# Power_Generation.net
KiCad netlist of a schematic drawn in Altium Designer
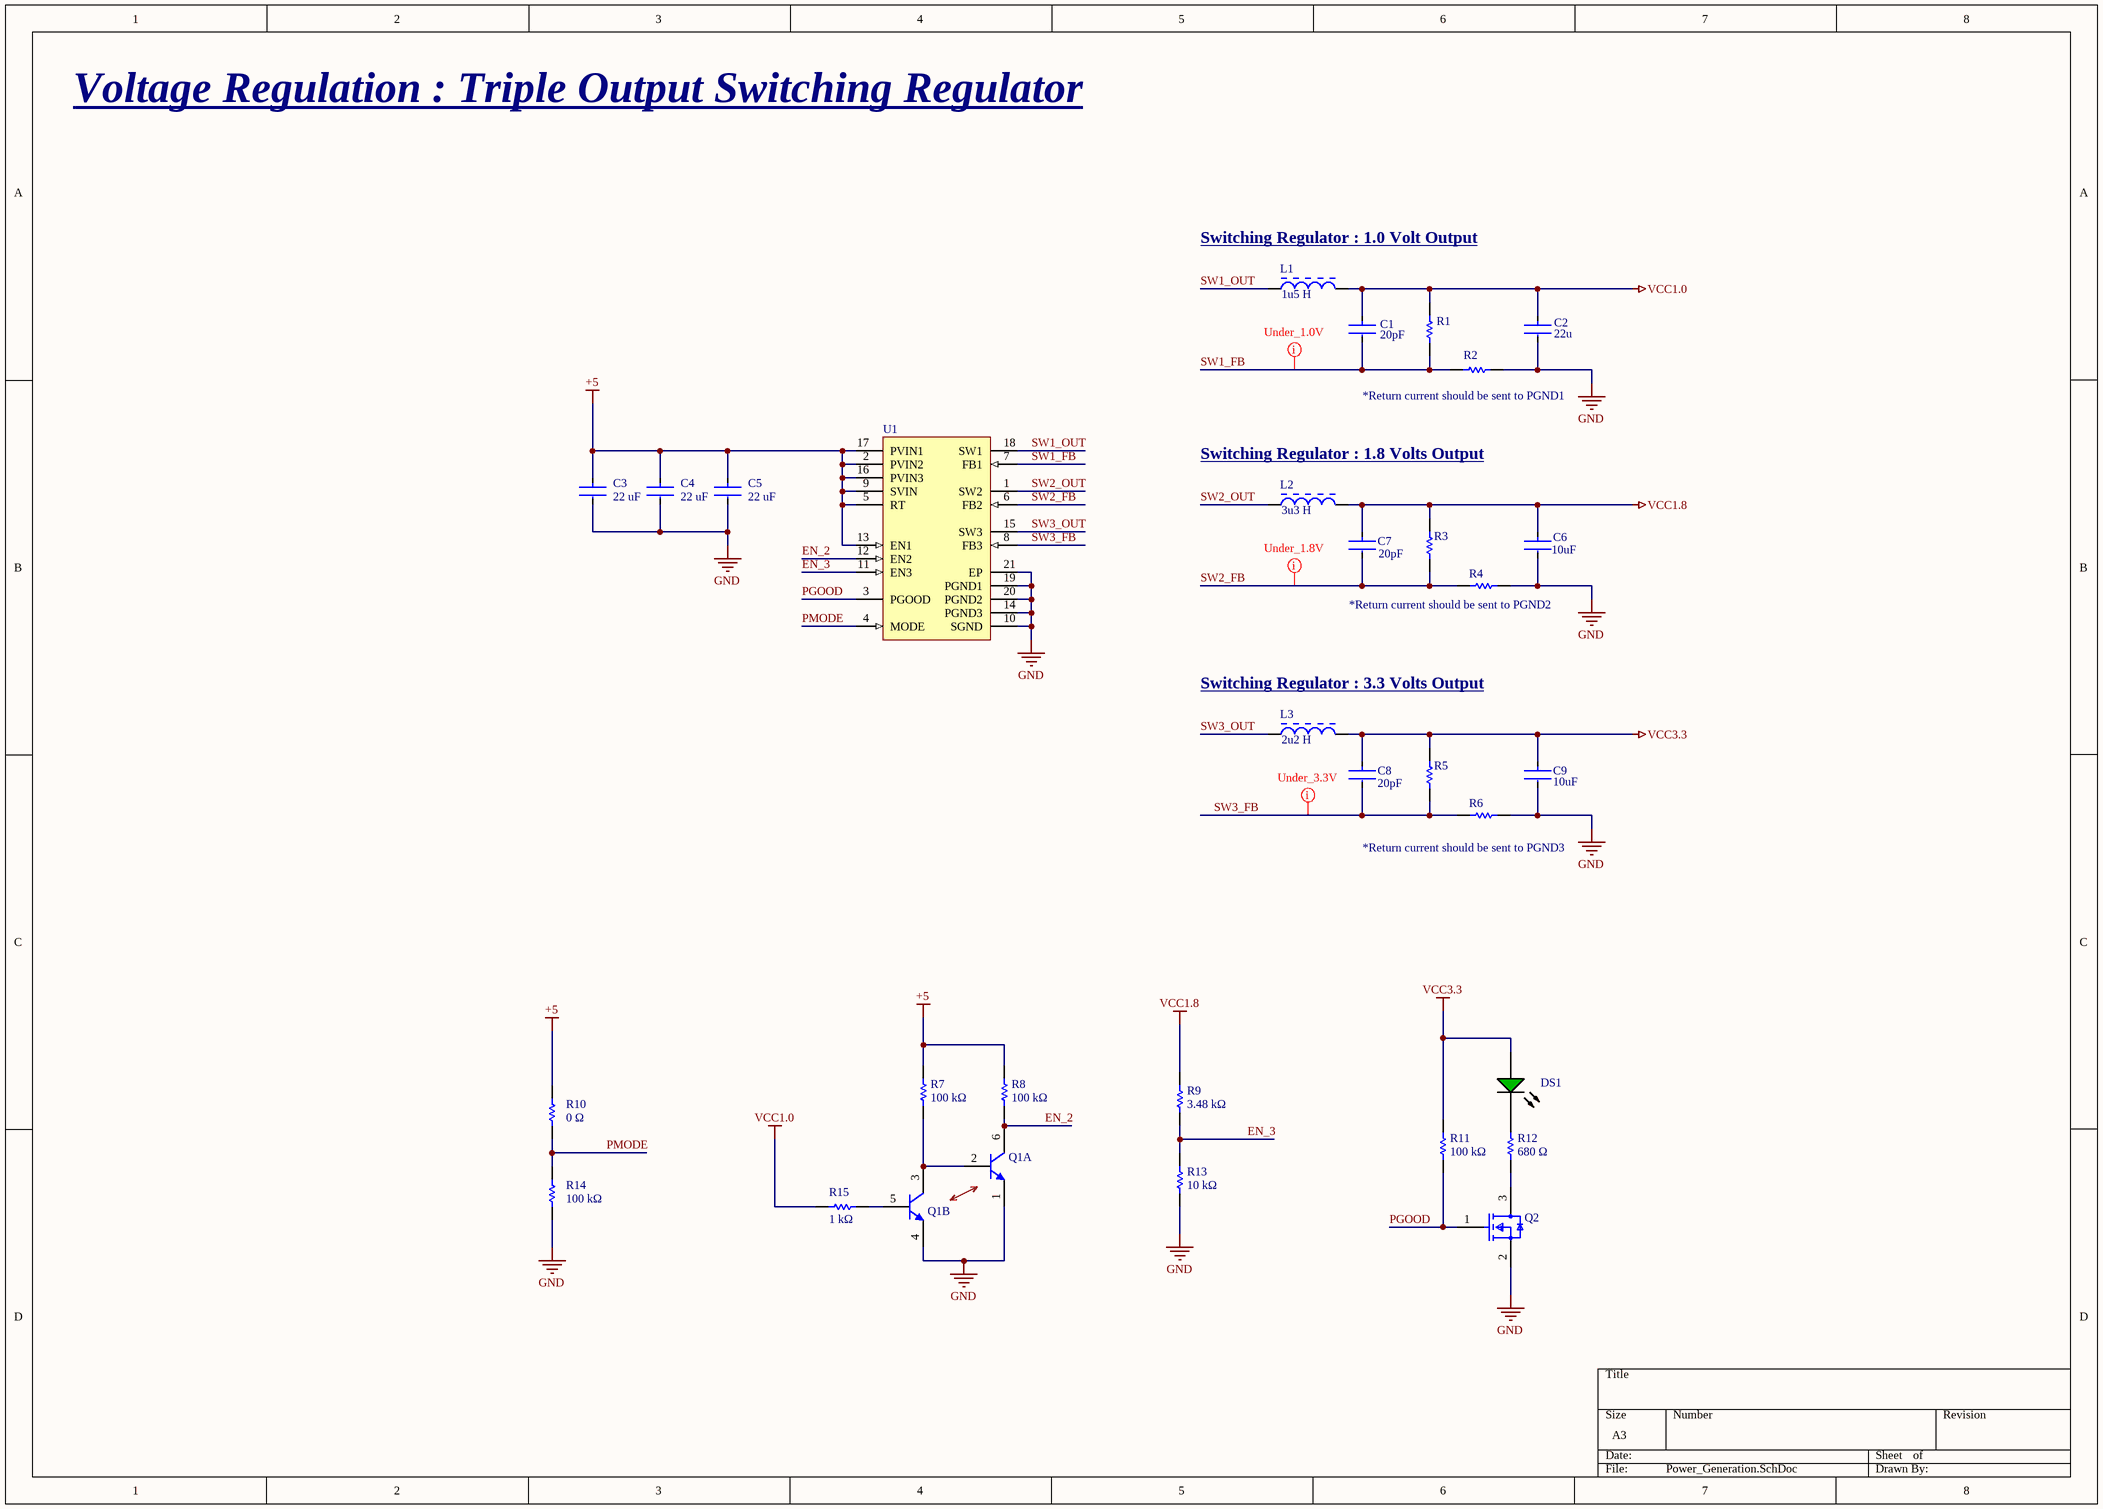
[diagram p0: Power_Generation.SchDoc]

(export (version "E")
  (design (tool "Eeschema 10.0.6"))
  (components
    (comp (ref "C1")
      (value "20pF")
      (footprint "FP-C0402-BB-MFG")
      (description "CAP CER 20PF 50V 5% NP0 0402")
      (fields
        (field (name "MANUFACTURER PART NUMBER") "C0402C200J5GACTU")
        (field (name "OCTOPART") "https://octopart.com/c0402c200j5gactu-kemet-9143900")
      )
      (libsource (lib "Altium Content Vault") (part "b4654b650e69147ec39a6b967a45e02"))
    )
    (comp (ref "C2")
      (value "GRM21BR60J226ME39L")
      (footprint "FP-GRM21B-0_15-MFG")
      (description "Chip Multilayer Ceramic Capacitors for General Purpose, 0805, 22uF, X5R, 15%, 20%, 6.3V")
      (fields
        (field (name "VOLTAGE") "6.3V")
        (field (name "TOLERANCE") "20%")
        (field (name "CAPACITANCE") "22u")
      )
      (libsource (lib "Altium Content Vault") (part "b4654b650e69147ec39a6b967a45e02"))
    )
    (comp (ref "C3")
      (value "GRM21BR60J226ME39L")
      (footprint "FP-GRM21B-0_15-MFG")
      (description "Chip Multilayer Ceramic Capacitors for General Purpose, 0805, 22uF, X5R, 15%, 20%, 6.3V")
      (fields
        (field (name "VOLTAGE") "6.3V")
        (field (name "TOLERANCE") "20%")
        (field (name "CAPACITANCE") "22 uF")
      )
      (libsource (lib "Altium Content Vault") (part "b4654b650e69147ec39a6b967a45e02"))
    )
    (comp (ref "C4")
      (value "GRM21BR60J226ME39L")
      (footprint "FP-GRM21B-0_15-MFG")
      (description "Chip Multilayer Ceramic Capacitors for General Purpose, 0805, 22uF, X5R, 15%, 20%, 6.3V")
      (fields
        (field (name "VOLTAGE") "6.3V")
        (field (name "TOLERANCE") "20%")
        (field (name "CAPACITANCE") "22 uF")
      )
      (libsource (lib "Altium Content Vault") (part "b4654b650e69147ec39a6b967a45e02"))
    )
    (comp (ref "C5")
      (value "GRM21BR60J226ME39L")
      (footprint "FP-GRM21B-0_15-MFG")
      (description "Chip Multilayer Ceramic Capacitors for General Purpose, 0805, 22uF, X5R, 15%, 20%, 6.3V")
      (fields
        (field (name "VOLTAGE") "6.3V")
        (field (name "TOLERANCE") "20%")
        (field (name "CAPACITANCE") "22 uF")
      )
      (libsource (lib "Altium Content Vault") (part "b4654b650e69147ec39a6b967a45e02"))
    )
    (comp (ref "C6")
      (value "GRM188R60J106ME47D")
      (footprint "FP-GRM188-0_1-e0_2_0_55-IPC_A")
      (description "Chip Multilayer Ceramic Capacitors for General Purpose, 0603, 10uF, X5R, 15%, 20%, 6.3V")
      (fields
        (field (name "CAPACITANCE") "10uF")
        (field (name "VOLTAGE") "6.3V")
        (field (name "TOLERANCE") "20%")
      )
      (libsource (lib "Altium Content Vault") (part "02cd4be3c70576c341d710602a673aa"))
    )
    (comp (ref "C7")
      (value "20pF")
      (footprint "FP-C0402-BB-MFG")
      (description "CAP CER 20PF 50V 5% NP0 0402")
      (fields
        (field (name "MANUFACTURER PART NUMBER") "C0402C200J5GACTU")
        (field (name "OCTOPART") "https://octopart.com/c0402c200j5gactu-kemet-9143900")
      )
      (libsource (lib "Altium Content Vault") (part "b4654b650e69147ec39a6b967a45e02"))
    )
    (comp (ref "C8")
      (value "20pF")
      (footprint "FP-C0402-BB-MFG")
      (description "CAP CER 20PF 50V 5% NP0 0402")
      (fields
        (field (name "MANUFACTURER PART NUMBER") "C0402C200J5GACTU")
        (field (name "OCTOPART") "https://octopart.com/c0402c200j5gactu-kemet-9143900")
      )
      (libsource (lib "Altium Content Vault") (part "b4654b650e69147ec39a6b967a45e02"))
    )
    (comp (ref "C9")
      (value "GRM188R60J106ME47D")
      (footprint "FP-GRM188-0_1-e0_2_0_55-IPC_A")
      (description "Chip Multilayer Ceramic Capacitors for General Purpose, 0603, 10uF, X5R, 15%, 20%, 6.3V")
      (fields
        (field (name "CAPACITANCE") "10uF")
        (field (name "VOLTAGE") "6.3V")
        (field (name "TOLERANCE") "20%")
      )
      (libsource (lib "Altium Content Vault") (part "02cd4be3c70576c341d710602a673aa"))
    )
    (comp (ref "DS1")
      (value "HSMG-C170")
      (footprint "AVAG-HSMX-C170_V")
      (description "Chip LED, Green, 2.2 V, -40 to 85 degC, 2-Pin SMD, Pb-Free, Tape and Reel")
      (fields (field (name "MANUFACTURER") "Avago"))
      (libsource (lib "Altium Content Vault") (part "LED_GREEN_A1K2-2"))
    )
    (comp (ref "L1")
      (value "SRN3015-1R5Y")
      (footprint "BOUR-SRN3015-2_V")
      (fields (field (name "MANUFACTURER") "Bourns") (field (name "INDUCTANCE") "1u5 H"))
      (libsource (lib "Altium Content Vault") (part "BOUR-IND-2A"))
    )
    (comp (ref "L2")
      (value "SRN3015-3R3M")
      (footprint "BOUR-SRN3015-2_V")
      (fields (field (name "MANUFACTURER") "Bourns") (field (name "INDUCTANCE") "3u3 H"))
      (libsource (lib "Altium Content Vault") (part "BOUR-IND-2A"))
    )
    (comp (ref "L3")
      (value "SRN3015-2R2M")
      (footprint "BOUR-SRN3015-2_V")
      (fields (field (name "MANUFACTURER") "Bourns") (field (name "INDUCTANCE") "2u2 H"))
      (libsource (lib "Altium Content Vault") (part "BOUR-IND-2A"))
    )
    (comp (ref "Q1")
      (value "SMBT3904DW1T1G")
      (footprint "ONSC-SOT-363-6-419B-02_W_V")
      (description "Dual General Purpose Transistors, 6-Pin SOT-363, Pb-Free, Tape and Reel")
      (fields (field (name "MANUFACTURER") "On Semiconductor"))
      (libsource (lib "Altium Content Vault") (part "ONSC-NPN_NPN-6_F"))
    )
    (comp (ref "Q2")
      (value "BSS138")
      (footprint "FP-318-08-IPC_B")
      (description "MOSFET N-CH 50V 220MA SOT-23")
      (libsource (lib "Altium Content Vault") (part "3b9c635fedb024a5347a57b145af9cc"))
    )
    (comp (ref "R1")
      (value "ERJ-3GEYJ303V")
      (footprint "RESC1608X55X30LL15T15")
      (fields (field (name "MANUFACTURER") "Panasonic"))
      (libsource (lib "Altium Content Vault") (part "RES"))
    )
    (comp (ref "R2")
      (value "ERJ1GNF1203C")
      (footprint "RESC0603X26X15LL03T05")
      (fields (field (name "MANUFACTURER") "Panasonic"))
      (libsource (lib "Altium Content Vault") (part "RES"))
    )
    (comp (ref "R3")
      (value "RK73H1JTTD1503F")
      (footprint "RESC1608X55X30LL20T10")
      (fields (field (name "MANUFACTURER") "KOA Speer"))
      (libsource (lib "Altium Content Vault") (part "RES"))
    )
    (comp (ref "R4")
      (value "ERJ1GNF1203C")
      (footprint "RESC0603X26X15LL03T05")
      (fields (field (name "MANUFACTURER") "Panasonic"))
      (libsource (lib "Altium Content Vault") (part "RES"))
    )
    (comp (ref "R5")
      (value "ERJ-3GEYJ184V")
      (footprint "RESC1608X55X30ML15T15")
      (fields (field (name "MANUFACTURER") "Panasonic"))
      (libsource (lib "Altium Content Vault") (part "RES"))
    )
    (comp (ref "R6")
      (value "ERJ-3EKF5762V")
      (footprint "RESC1608X55X30ML15T15")
      (fields (field (name "MANUFACTURER") "Panasonic"))
      (libsource (lib "Altium Content Vault") (part "RES"))
    )
    (comp (ref "R7")
      (value "RC0603JR-070RL")
      (footprint "RESC1608X55X25ML10T15")
      (description "Chip Resistor, 0 Ohm, +/- 5%, 0.1 W, -55 to 155 degC, 0603 (1608 Metric), RoHS, Tape and Reel")
      (fields
        (field (name "TOLERANCE") "5%")
        (field (name "RESISTANCE") "100 kΩ")
        (field (name "MANUFACTURER") "Yageo")
      )
      (libsource (lib "Altium Content Vault") (part "RES-2"))
    )
    (comp (ref "R8")
      (value "RC0603JR-070RL")
      (footprint "RESC1608X55X25ML10T15")
      (description "Chip Resistor, 0 Ohm, +/- 5%, 0.1 W, -55 to 155 degC, 0603 (1608 Metric), RoHS, Tape and Reel")
      (fields
        (field (name "TOLERANCE") "5%")
        (field (name "RESISTANCE") "100 kΩ")
        (field (name "MANUFACTURER") "Yageo")
      )
      (libsource (lib "Altium Content Vault") (part "RES-2"))
    )
    (comp (ref "R9")
      (value "RC0603JR-070RL")
      (footprint "RESC1608X55X25ML10T15")
      (description "Chip Resistor, 0 Ohm, +/- 5%, 0.1 W, -55 to 155 degC, 0603 (1608 Metric), RoHS, Tape and Reel")
      (fields
        (field (name "TOLERANCE") "5%")
        (field (name "RESISTANCE") "3.48 kΩ")
        (field (name "MANUFACTURER") "Yageo")
      )
      (libsource (lib "Altium Content Vault") (part "RES-2"))
    )
    (comp (ref "R10")
      (value "RC0603JR-070RL")
      (footprint "RESC1608X55X25NL10T15")
      (description "Chip Resistor, 0 Ohm, +/- 5%, 0.1 W, -55 to 155 degC, 0603 (1608 Metric), RoHS, Tape and Reel")
      (fields
        (field (name "TOLERANCE") "5%")
        (field (name "RESISTANCE") "0 Ω")
        (field (name "MANUFACTURER") "Yageo")
      )
      (libsource (lib "Altium Content Vault") (part "RES-2"))
    )
    (comp (ref "R11")
      (value "RC0603JR-070RL")
      (footprint "RESC1608X55X25ML10T15")
      (description "Chip Resistor, 0 Ohm, +/- 5%, 0.1 W, -55 to 155 degC, 0603 (1608 Metric), RoHS, Tape and Reel")
      (fields
        (field (name "TOLERANCE") "5%")
        (field (name "RESISTANCE") "100 kΩ")
        (field (name "MANUFACTURER") "Yageo")
      )
      (libsource (lib "Altium Content Vault") (part "RES-2"))
    )
    (comp (ref "R12")
      (value "RC0603JR-070RL")
      (footprint "RESC1608X55X25ML10T15")
      (description "Chip Resistor, 0 Ohm, +/- 5%, 0.1 W, -55 to 155 degC, 0603 (1608 Metric), RoHS, Tape and Reel")
      (fields
        (field (name "TOLERANCE") "5%")
        (field (name "RESISTANCE") "680 Ω")
        (field (name "MANUFACTURER") "Yageo")
      )
      (libsource (lib "Altium Content Vault") (part "RES-2"))
    )
    (comp (ref "R13")
      (value "RC0603JR-070RL")
      (footprint "RESC1608X55X25ML10T15")
      (description "Chip Resistor, 0 Ohm, +/- 5%, 0.1 W, -55 to 155 degC, 0603 (1608 Metric), RoHS, Tape and Reel")
      (fields
        (field (name "TOLERANCE") "5%")
        (field (name "RESISTANCE") "10 kΩ")
        (field (name "MANUFACTURER") "Yageo")
      )
      (libsource (lib "Altium Content Vault") (part "RES-2"))
    )
    (comp (ref "R14")
      (value "RC0603JR-070RL")
      (footprint "RESC1608X55X25NL10T15")
      (description "Chip Resistor, 0 Ohm, +/- 5%, 0.1 W, -55 to 155 degC, 0603 (1608 Metric), RoHS, Tape and Reel")
      (fields
        (field (name "TOLERANCE") "5%")
        (field (name "RESISTANCE") "100 kΩ")
        (field (name "MANUFACTURER") "Yageo")
      )
      (libsource (lib "Altium Content Vault") (part "RES-2"))
    )
    (comp (ref "R15")
      (value "RC0603JR-070RL")
      (footprint "RESC1608X55X25ML10T15")
      (description "Chip Resistor, 0 Ohm, +/- 5%, 0.1 W, -55 to 155 degC, 0603 (1608 Metric), RoHS, Tape and Reel")
      (fields
        (field (name "TOLERANCE") "5%")
        (field (name "RESISTANCE") "1 kΩ")
        (field (name "MANUFACTURER") "Yageo")
      )
      (libsource (lib "Altium Content Vault") (part "RES-2"))
    )
    (comp (ref "U1")
      (value "LTC3569EUD#TRPBF")
      (footprint "LT-UD-20_M")
      (fields (field (name "MANUFACTURER") "Linear Technology"))
      (libsource (lib "Altium Content Vault") (part "LT-LTC3569-UD-20"))
    )
  )
  (nets
    (net (code "1") (name "+5") (class "Default")
      (node (ref "C3") (pin "1") (pinfunction "1_1") (pintype "passive"))
      (node (ref "C4") (pin "1") (pinfunction "1_1") (pintype "passive"))
      (node (ref "C5") (pin "1") (pinfunction "1_1") (pintype "passive"))
      (node (ref "R10") (pin "2") (pinfunction "2_2") (pintype "passive"))
      (node (ref "R7") (pin "2") (pinfunction "2_2") (pintype "passive"))
      (node (ref "R8") (pin "2") (pinfunction "2_2") (pintype "passive"))
      (node (ref "U1") (pin "13") (pinfunction "EN1_13") (pintype "input"))
      (node (ref "U1") (pin "16") (pinfunction "PVIN3_16") (pintype "power_in"))
      (node (ref "U1") (pin "17") (pinfunction "PVIN1_17") (pintype "power_in"))
      (node (ref "U1") (pin "2") (pinfunction "PVIN2_2") (pintype "power_in"))
      (node (ref "U1") (pin "5") (pinfunction "RT_5") (pintype "passive"))
      (node (ref "U1") (pin "9") (pinfunction "SVIN_9") (pintype "power_in"))
    )
    (net (code "2") (name "/EN_2") (class "Default")
      (node (ref "Q1") (pin "6") (pinfunction "C_6") (pintype "passive"))
      (node (ref "R8") (pin "1") (pinfunction "1_1") (pintype "passive"))
      (node (ref "U1") (pin "12") (pinfunction "EN2_12") (pintype "input"))
    )
    (net (code "3") (name "/EN_3") (class "Default")
      (node (ref "R13") (pin "1") (pinfunction "1_1") (pintype "passive"))
      (node (ref "R9") (pin "2") (pinfunction "2_2") (pintype "passive"))
      (node (ref "U1") (pin "11") (pinfunction "EN3_11") (pintype "input"))
    )
    (net (code "4") (name "/PGOOD") (class "Default")
      (node (ref "Q2") (pin "1") (pinfunction "G_1") (pintype "passive"))
      (node (ref "R11") (pin "2") (pinfunction "2_2") (pintype "passive"))
      (node (ref "U1") (pin "3") (pinfunction "PGOOD_3") (pintype "open_collector"))
    )
    (net (code "5") (name "/PMODE") (class "Default")
      (node (ref "R10") (pin "1") (pinfunction "1_1") (pintype "passive"))
      (node (ref "R14") (pin "2") (pinfunction "2_2") (pintype "passive"))
      (node (ref "U1") (pin "4") (pinfunction "MODE_4") (pintype "input"))
    )
    (net (code "6") (name "/SW1_FB") (class "Default")
      (node (ref "C1") (pin "2") (pinfunction "2_2") (pintype "passive"))
      (node (ref "R1") (pin "1") (pinfunction "1_1") (pintype "passive"))
      (node (ref "R2") (pin "1") (pinfunction "1_1") (pintype "passive"))
      (node (ref "U1") (pin "7") (pinfunction "FB1_7") (pintype "input"))
    )
    (net (code "7") (name "/SW1_OUT") (class "Default")
      (node (ref "L1") (pin "1") (pinfunction "1_1") (pintype "passive"))
      (node (ref "U1") (pin "18") (pinfunction "SW1_18") (pintype "power_in"))
    )
    (net (code "8") (name "/SW2_FB") (class "Default")
      (node (ref "C7") (pin "2") (pinfunction "2_2") (pintype "passive"))
      (node (ref "R3") (pin "1") (pinfunction "1_1") (pintype "passive"))
      (node (ref "R4") (pin "1") (pinfunction "1_1") (pintype "passive"))
      (node (ref "U1") (pin "6") (pinfunction "FB2_6") (pintype "input"))
    )
    (net (code "9") (name "/SW2_OUT") (class "Default")
      (node (ref "L2") (pin "1") (pinfunction "1_1") (pintype "passive"))
      (node (ref "U1") (pin "1") (pinfunction "SW2_1") (pintype "power_in"))
    )
    (net (code "10") (name "/SW3_FB") (class "Default")
      (node (ref "C8") (pin "2") (pinfunction "2_2") (pintype "passive"))
      (node (ref "R5") (pin "1") (pinfunction "1_1") (pintype "passive"))
      (node (ref "R6") (pin "1") (pinfunction "1_1") (pintype "passive"))
      (node (ref "U1") (pin "8") (pinfunction "FB3_8") (pintype "input"))
    )
    (net (code "11") (name "/SW3_OUT") (class "Default")
      (node (ref "L3") (pin "1") (pinfunction "1_1") (pintype "passive"))
      (node (ref "U1") (pin "15") (pinfunction "SW3_15") (pintype "power_in"))
    )
    (net (code "12") (name "GND") (class "Default")
      (node (ref "C2") (pin "2") (pinfunction "2_2") (pintype "passive"))
      (node (ref "C3") (pin "2") (pinfunction "2_2") (pintype "passive"))
      (node (ref "C4") (pin "2") (pinfunction "2_2") (pintype "passive"))
      (node (ref "C5") (pin "2") (pinfunction "2_2") (pintype "passive"))
      (node (ref "C6") (pin "2") (pinfunction "2_2") (pintype "passive"))
      (node (ref "C9") (pin "2") (pinfunction "2_2") (pintype "passive"))
      (node (ref "Q1") (pin "1") (pinfunction "E_1") (pintype "passive"))
      (node (ref "Q1") (pin "4") (pinfunction "E_4") (pintype "passive"))
      (node (ref "Q2") (pin "2") (pinfunction "S_2") (pintype "passive"))
      (node (ref "R13") (pin "2") (pinfunction "2_2") (pintype "passive"))
      (node (ref "R14") (pin "1") (pinfunction "1_1") (pintype "passive"))
      (node (ref "R2") (pin "2") (pinfunction "2_2") (pintype "passive"))
      (node (ref "R4") (pin "2") (pinfunction "2_2") (pintype "passive"))
      (node (ref "R6") (pin "2") (pinfunction "2_2") (pintype "passive"))
      (node (ref "U1") (pin "10") (pinfunction "SGND_10") (pintype "power_in"))
      (node (ref "U1") (pin "14") (pinfunction "PGND3_14") (pintype "power_in"))
      (node (ref "U1") (pin "19") (pinfunction "PGND1_19") (pintype "power_in"))
      (node (ref "U1") (pin "20") (pinfunction "PGND2_20") (pintype "power_in"))
      (node (ref "U1") (pin "21") (pinfunction "EP_21") (pintype "power_in"))
    )
    (net (code "13") (name "Net-(DS1-K)") (class "Default")
      (node (ref "DS1") (pin "2") (pinfunction "K_2") (pintype "passive"))
      (node (ref "R12") (pin "1") (pinfunction "1_1") (pintype "passive"))
    )
    (net (code "14") (name "Net-(Q1A-B)") (class "Default")
      (node (ref "Q1") (pin "2") (pinfunction "B_2") (pintype "passive"))
      (node (ref "Q1") (pin "3") (pinfunction "C_3") (pintype "passive"))
      (node (ref "R7") (pin "1") (pinfunction "1_1") (pintype "passive"))
    )
    (net (code "15") (name "Net-(Q1B-B)") (class "Default")
      (node (ref "Q1") (pin "5") (pinfunction "B_5") (pintype "passive"))
      (node (ref "R15") (pin "1") (pinfunction "1_1") (pintype "passive"))
    )
    (net (code "16") (name "Net-(Q2-D)") (class "Default")
      (node (ref "Q2") (pin "3") (pinfunction "D_3") (pintype "passive"))
      (node (ref "R12") (pin "2") (pinfunction "2_2") (pintype "passive"))
    )
    (net (code "17") (name "VCC1.0") (class "Default")
      (node (ref "C1") (pin "1") (pinfunction "1_1") (pintype "passive"))
      (node (ref "C2") (pin "1") (pinfunction "1_1") (pintype "passive"))
      (node (ref "L1") (pin "2") (pinfunction "2_2") (pintype "passive"))
      (node (ref "R1") (pin "2") (pinfunction "2_2") (pintype "passive"))
      (node (ref "R15") (pin "2") (pinfunction "2_2") (pintype "passive"))
    )
    (net (code "18") (name "VCC1.8") (class "Default")
      (node (ref "C6") (pin "1") (pinfunction "1_1") (pintype "passive"))
      (node (ref "C7") (pin "1") (pinfunction "1_1") (pintype "passive"))
      (node (ref "L2") (pin "2") (pinfunction "2_2") (pintype "passive"))
      (node (ref "R3") (pin "2") (pinfunction "2_2") (pintype "passive"))
      (node (ref "R9") (pin "1") (pinfunction "1_1") (pintype "passive"))
    )
    (net (code "19") (name "VCC3.3") (class "Default")
      (node (ref "C8") (pin "1") (pinfunction "1_1") (pintype "passive"))
      (node (ref "C9") (pin "1") (pinfunction "1_1") (pintype "passive"))
      (node (ref "DS1") (pin "1") (pinfunction "A_1") (pintype "passive"))
      (node (ref "L3") (pin "2") (pinfunction "2_2") (pintype "passive"))
      (node (ref "R11") (pin "1") (pinfunction "1_1") (pintype "passive"))
      (node (ref "R5") (pin "2") (pinfunction "2_2") (pintype "passive"))
    )
  )
)
